# sterowanie_przeka_nik.net
KiCad netlist of a schematic drawn in EAGLE
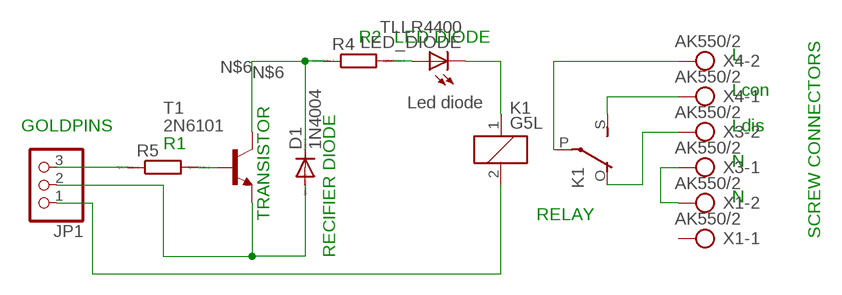
[diagram p0: schematic, sheet 1]

(export (version "E")
  (design (tool "Eeschema 10.0.6"))
  (components
    (comp (ref "D1")
      (value "1N4004")
      (footprint "eagle-import:DO41-10")
      (libsource (lib "eagle-import") (part "1N4004"))
    )
    (comp (ref "JP1")
      (value "PINHD-1X3")
      (footprint "eagle-import:1X03")
      (libsource (lib "eagle-import") (part "PINHD-1X3"))
    )
    (comp (ref "K1")
      (value "G5L")
      (footprint "eagle-import:G5LE")
      (libsource (lib "eagle-import") (part "G5L"))
    )
    (comp (ref "LED_DIODE")
      (value "TLLR4400")
      (footprint "eagle-import:LED3MM")
      (fields (field (name "MF") "VISHAY SEMICONDUCTOR") (field (name "MF_1") "Led diode"))
      (libsource (lib "eagle-import") (part "TLLR4400"))
    )
    (comp (ref "R4")
      (value "R0207/10")
      (footprint "eagle-import:0207_10")
      (libsource (lib "eagle-import") (part "R0207/10"))
    )
    (comp (ref "R5")
      (value "R0207/10")
      (footprint "eagle-import:0207_10")
      (libsource (lib "eagle-import") (part "R0207/10"))
    )
    (comp (ref "T1")
      (value "2N6101")
      (footprint "eagle-import:TO220")
      (libsource (lib "eagle-import") (part "2N6101"))
    )
    (comp (ref "X1")
      (value "AK550/2")
      (footprint "eagle-import:AK550_2")
      (libsource (lib "eagle-import") (part "AK550/2"))
    )
    (comp (ref "X3")
      (value "AK550/2")
      (footprint "eagle-import:AK550_2")
      (libsource (lib "eagle-import") (part "AK550/2"))
    )
    (comp (ref "X4")
      (value "AK550/2")
      (footprint "eagle-import:AK550_2")
      (libsource (lib "eagle-import") (part "AK550/2"))
    )
  )
  (nets
    (net (code "1") (name "/N$6") (class "Default")
      (node (ref "D1") (pin "C") (pinfunction "C_C") (pintype "passive"))
      (node (ref "R4") (pin "1") (pinfunction "1_1") (pintype "passive"))
      (node (ref "T1") (pin "2") (pinfunction "C_2") (pintype "passive"))
    )
    (net (code "2") (name "Net-(JP1-Pad1)") (class "Default")
      (node (ref "JP1") (pin "1") (pinfunction "1_1") (pintype "passive"))
      (node (ref "K1") (pin "2") (pinfunction "2_2") (pintype "passive"))
    )
    (net (code "3") (name "Net-(JP1-Pad3)") (class "Default")
      (node (ref "JP1") (pin "3") (pinfunction "3_3") (pintype "passive"))
      (node (ref "R5") (pin "1") (pinfunction "1_1") (pintype "passive"))
    )
    (net (code "4") (name "Net-(LED_DIODE-C)") (class "Default")
      (node (ref "K1") (pin "1") (pinfunction "1_1") (pintype "passive"))
      (node (ref "LED_DIODE") (pin "K") (pinfunction "C_K") (pintype "passive"))
    )
    (net (code "5") (name "Net-(LED_DIODE-PadA)") (class "Default")
      (node (ref "LED_DIODE") (pin "A") (pinfunction "A_A") (pintype "passive"))
      (node (ref "R4") (pin "2") (pinfunction "2_2") (pintype "passive"))
    )
    (net (code "6") (name "Net-(T1-B)") (class "Default")
      (node (ref "R5") (pin "2") (pinfunction "2_2") (pintype "passive"))
      (node (ref "T1") (pin "1") (pinfunction "B_1") (pintype "passive"))
    )
    (net (code "7") (name "Net-(T1-E)") (class "Default")
      (node (ref "D1") (pin "A") (pinfunction "A_A") (pintype "passive"))
      (node (ref "JP1") (pin "2") (pinfunction "2_2") (pintype "passive"))
      (node (ref "T1") (pin "3") (pinfunction "E_3") (pintype "passive"))
    )
    (net (code "8") (name "Net-(X1B-KL)") (class "Default")
      (node (ref "X1") (pin "2") (pinfunction "KL_2") (pintype "passive"))
      (node (ref "X3") (pin "1") (pinfunction "KL_1") (pintype "passive"))
    )
    (net (code "9") (name "Net-(X3B-KL)") (class "Default")
      (node (ref "K1") (pin "O") (pinfunction "O_O") (pintype "passive"))
      (node (ref "X3") (pin "2") (pinfunction "KL_2") (pintype "passive"))
    )
    (net (code "10") (name "Net-(X4A-KL)") (class "Default")
      (node (ref "K1") (pin "S") (pinfunction "S_S") (pintype "passive"))
      (node (ref "X4") (pin "1") (pinfunction "KL_1") (pintype "passive"))
    )
    (net (code "11") (name "Net-(X4B-KL)") (class "Default")
      (node (ref "K1") (pin "P") (pinfunction "P_P") (pintype "passive"))
      (node (ref "X4") (pin "2") (pinfunction "KL_2") (pintype "passive"))
    )
    (net (code "12") (name "unconnected-(X1A-KL-Pad1)") (class "Default")
      (node (ref "X1") (pin "1") (pinfunction "KL_1") (pintype "passive"))
    )
  )
)
